# team_flag.net
KiCad netlist of a schematic drawn in EAGLE
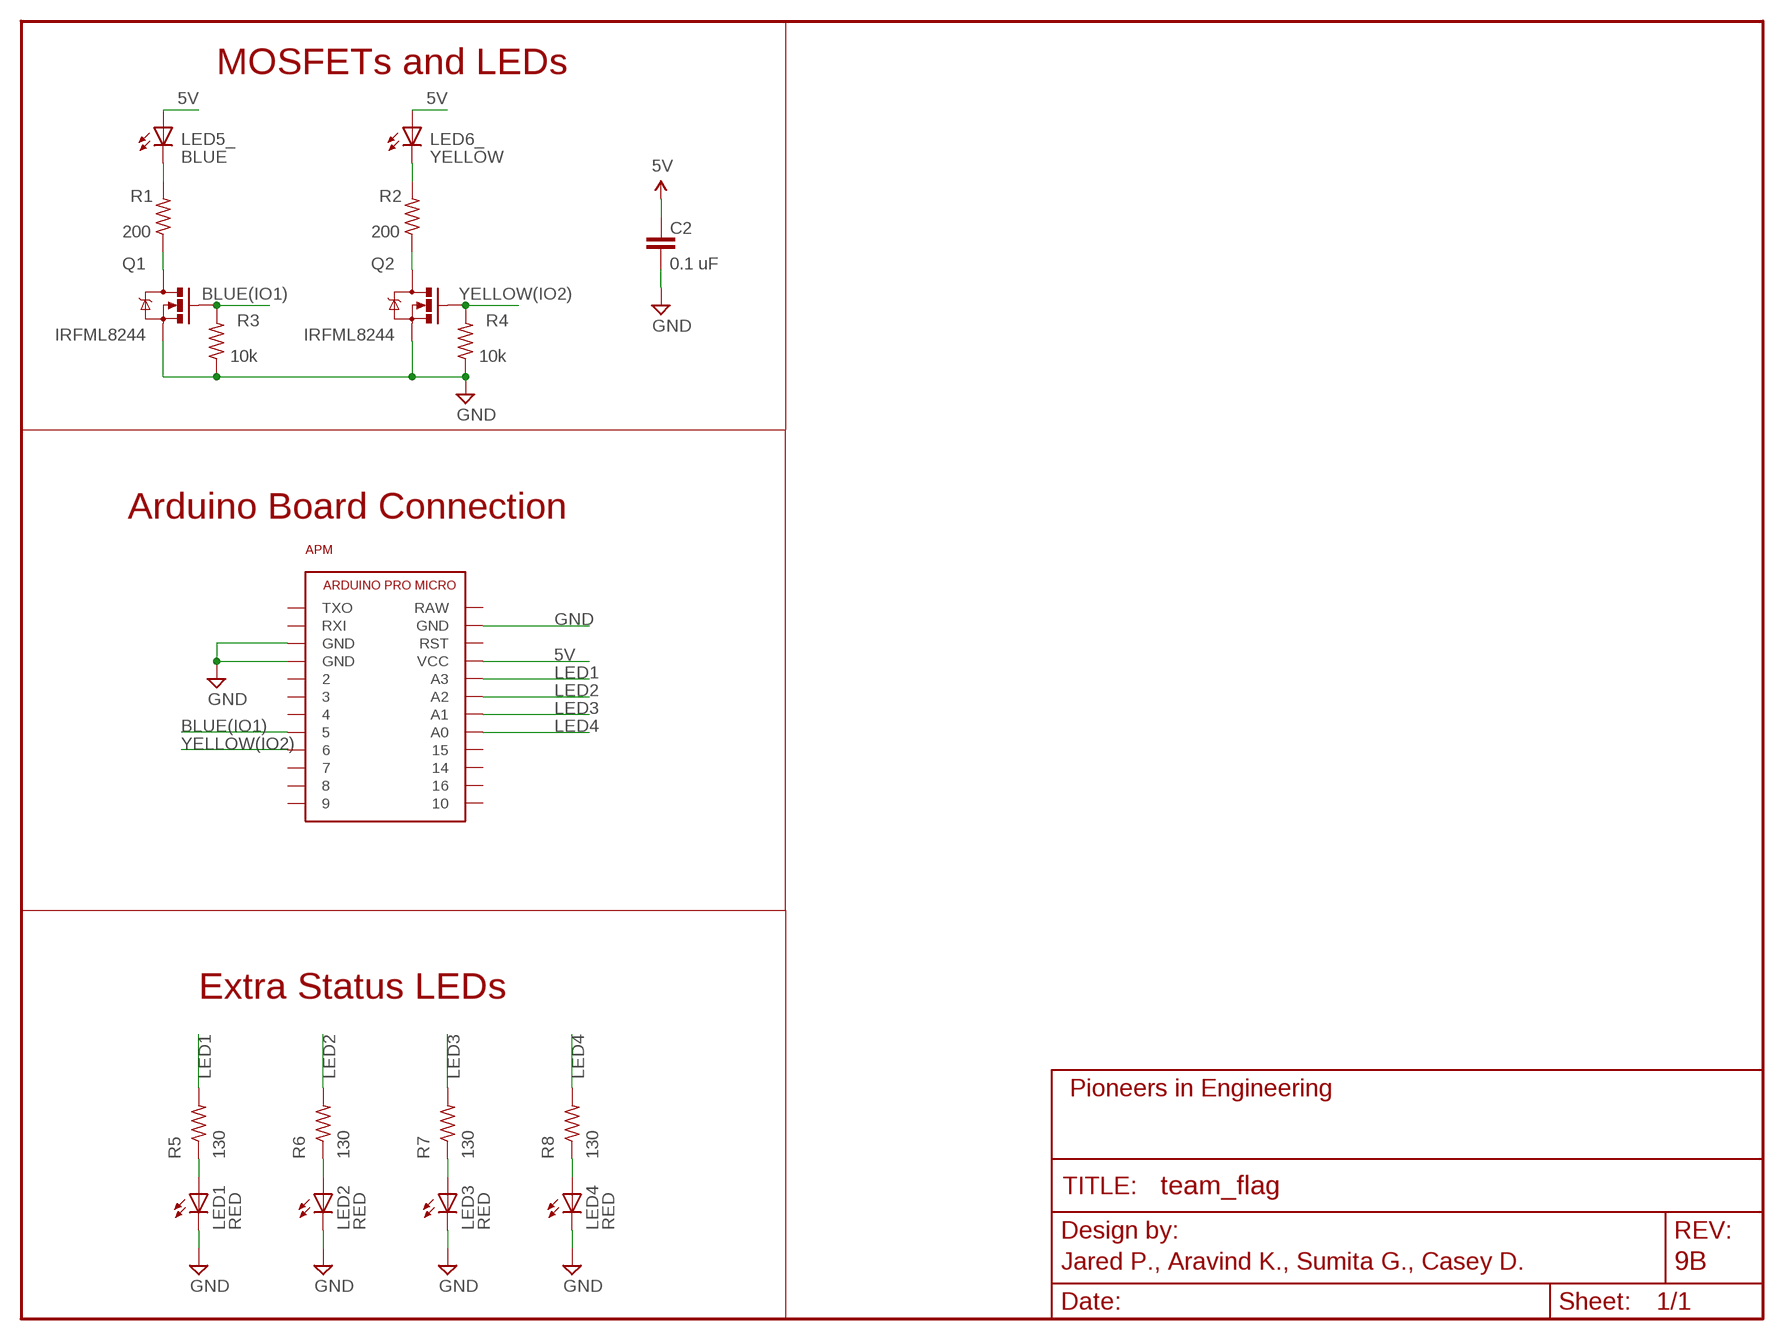
[diagram p0: schematic, sheet 1]

(export (version "E")
  (design (tool "Eeschema 10.0.6"))
  (components
    (comp (ref "APM")
      (value "ARDUINO_PRO_MICRO")
      (footprint "eagle-import:ARDUINO_PRO_MICRO")
      (libsource (lib "eagle-import") (part "ARDUINO_PRO_MICRO"))
    )
    (comp (ref "C2")
      (value "0.1 uF")
      (footprint "eagle-import:0603-CAP")
      (libsource (lib "eagle-import") (part "CAP0603-CAP"))
    )
    (comp (ref "LED1")
      (value "RED")
      (footprint "eagle-import:LED-0805")
      (libsource (lib "eagle-import") (part "LED0805"))
    )
    (comp (ref "LED2")
      (value "RED")
      (footprint "eagle-import:LED-0805")
      (libsource (lib "eagle-import") (part "LED0805"))
    )
    (comp (ref "LED3")
      (value "RED")
      (footprint "eagle-import:LED-0805")
      (libsource (lib "eagle-import") (part "LED0805"))
    )
    (comp (ref "LED4")
      (value "RED")
      (footprint "eagle-import:LED-0805")
      (libsource (lib "eagle-import") (part "LED0805"))
    )
    (comp (ref "LED5_")
      (value "BLUE")
      (footprint "eagle-import:LED5MM-NOFLAT")
      (libsource (lib "eagle-import") (part "LEDLED5MM-NOFLAT"))
    )
    (comp (ref "LED6_")
      (value "YELLOW")
      (footprint "eagle-import:LED5MM-NOFLAT")
      (libsource (lib "eagle-import") (part "LEDLED5MM-NOFLAT"))
    )
    (comp (ref "Q1")
      (value "IRFML8244")
      (footprint "eagle-import:SOT23-3")
      (libsource (lib "eagle-import") (part "MOSFET-NCHANNELSMD"))
    )
    (comp (ref "Q2")
      (value "IRFML8244")
      (footprint "eagle-import:SOT23-3")
      (libsource (lib "eagle-import") (part "MOSFET-NCHANNELSMD"))
    )
    (comp (ref "R1")
      (value "200")
      (footprint "eagle-import:R0603")
      (libsource (lib "eagle-import") (part "R-US_R0603"))
    )
    (comp (ref "R2")
      (value "200")
      (footprint "eagle-import:R0603")
      (libsource (lib "eagle-import") (part "R-US_R0603"))
    )
    (comp (ref "R3")
      (value "10k")
      (footprint "eagle-import:R0603")
      (libsource (lib "eagle-import") (part "R-US_R0603"))
    )
    (comp (ref "R4")
      (value "10k")
      (footprint "eagle-import:R0603")
      (libsource (lib "eagle-import") (part "R-US_R0603"))
    )
    (comp (ref "R5")
      (value "130")
      (footprint "eagle-import:R0603")
      (libsource (lib "eagle-import") (part "R-US_R0603"))
    )
    (comp (ref "R6")
      (value "130")
      (footprint "eagle-import:R0603")
      (libsource (lib "eagle-import") (part "R-US_R0603"))
    )
    (comp (ref "R7")
      (value "130")
      (footprint "eagle-import:R0603")
      (libsource (lib "eagle-import") (part "R-US_R0603"))
    )
    (comp (ref "R8")
      (value "130")
      (footprint "eagle-import:R0603")
      (libsource (lib "eagle-import") (part "R-US_R0603"))
    )
  )
  (nets
    (net (code "1") (name "/BLUE(IO1)") (class "Default")
      (node (ref "APM") (pin "5") (pinfunction "5_5") (pintype "bidirectional"))
      (node (ref "Q1") (pin "1") (pinfunction "G_1") (pintype "passive"))
      (node (ref "R3") (pin "2") (pinfunction "2_2") (pintype "passive"))
    )
    (net (code "2") (name "/LED1") (class "Default")
      (node (ref "APM") (pin "A3") (pinfunction "A3_A3") (pintype "bidirectional"))
      (node (ref "R5") (pin "2") (pinfunction "2_2") (pintype "passive"))
    )
    (net (code "3") (name "/LED2") (class "Default")
      (node (ref "APM") (pin "A2") (pinfunction "A2_A2") (pintype "bidirectional"))
      (node (ref "R6") (pin "2") (pinfunction "2_2") (pintype "passive"))
    )
    (net (code "4") (name "/LED3") (class "Default")
      (node (ref "APM") (pin "A1") (pinfunction "A1_A1") (pintype "bidirectional"))
      (node (ref "R7") (pin "2") (pinfunction "2_2") (pintype "passive"))
    )
    (net (code "5") (name "/LED4") (class "Default")
      (node (ref "APM") (pin "A0") (pinfunction "A0_A0") (pintype "bidirectional"))
      (node (ref "R8") (pin "2") (pinfunction "2_2") (pintype "passive"))
    )
    (net (code "6") (name "/YELLOW(IO2)") (class "Default")
      (node (ref "APM") (pin "6") (pinfunction "6_6") (pintype "bidirectional"))
      (node (ref "Q2") (pin "1") (pinfunction "G_1") (pintype "passive"))
      (node (ref "R4") (pin "2") (pinfunction "2_2") (pintype "passive"))
    )
    (net (code "7") (name "5V") (class "Default")
      (node (ref "APM") (pin "VCC") (pinfunction "VCC_VCC") (pintype "bidirectional"))
      (node (ref "C2") (pin "1") (pinfunction "1_1") (pintype "passive"))
      (node (ref "LED5_") (pin "A") (pinfunction "A_A") (pintype "passive"))
      (node (ref "LED6_") (pin "A") (pinfunction "A_A") (pintype "passive"))
    )
    (net (code "8") (name "GND") (class "Default")
      (node (ref "APM") (pin "GND@0") (pinfunction "GND_GND@0") (pintype "bidirectional"))
      (node (ref "APM") (pin "GND@1") (pinfunction "GND_GND@1") (pintype "bidirectional"))
      (node (ref "APM") (pin "GND@2") (pinfunction "GND_GND@2") (pintype "bidirectional"))
      (node (ref "C2") (pin "2") (pinfunction "2_2") (pintype "passive"))
      (node (ref "LED1") (pin "C") (pinfunction "C_C") (pintype "passive"))
      (node (ref "LED2") (pin "C") (pinfunction "C_C") (pintype "passive"))
      (node (ref "LED3") (pin "C") (pinfunction "C_C") (pintype "passive"))
      (node (ref "LED4") (pin "C") (pinfunction "C_C") (pintype "passive"))
      (node (ref "Q1") (pin "2") (pinfunction "S_2") (pintype "passive"))
      (node (ref "Q2") (pin "2") (pinfunction "S_2") (pintype "passive"))
      (node (ref "R3") (pin "1") (pinfunction "1_1") (pintype "passive"))
      (node (ref "R4") (pin "1") (pinfunction "1_1") (pintype "passive"))
    )
    (net (code "9") (name "Net-(LED1-PadA)") (class "Default")
      (node (ref "LED1") (pin "A") (pinfunction "A_A") (pintype "passive"))
      (node (ref "R5") (pin "1") (pinfunction "1_1") (pintype "passive"))
    )
    (net (code "10") (name "Net-(LED2-PadA)") (class "Default")
      (node (ref "LED2") (pin "A") (pinfunction "A_A") (pintype "passive"))
      (node (ref "R6") (pin "1") (pinfunction "1_1") (pintype "passive"))
    )
    (net (code "11") (name "Net-(LED3-PadA)") (class "Default")
      (node (ref "LED3") (pin "A") (pinfunction "A_A") (pintype "passive"))
      (node (ref "R7") (pin "1") (pinfunction "1_1") (pintype "passive"))
    )
    (net (code "12") (name "Net-(LED4-PadA)") (class "Default")
      (node (ref "LED4") (pin "A") (pinfunction "A_A") (pintype "passive"))
      (node (ref "R8") (pin "1") (pinfunction "1_1") (pintype "passive"))
    )
    (net (code "13") (name "Net-(LED5_-C)") (class "Default")
      (node (ref "LED5_") (pin "K") (pinfunction "C_K") (pintype "passive"))
      (node (ref "R1") (pin "2") (pinfunction "2_2") (pintype "passive"))
    )
    (net (code "14") (name "Net-(LED6_-C)") (class "Default")
      (node (ref "LED6_") (pin "K") (pinfunction "C_K") (pintype "passive"))
      (node (ref "R2") (pin "2") (pinfunction "2_2") (pintype "passive"))
    )
    (net (code "15") (name "Net-(Q1-D)") (class "Default")
      (node (ref "Q1") (pin "3") (pinfunction "D_3") (pintype "passive"))
      (node (ref "R1") (pin "1") (pinfunction "1_1") (pintype "passive"))
    )
    (net (code "16") (name "Net-(Q2-D)") (class "Default")
      (node (ref "Q2") (pin "3") (pinfunction "D_3") (pintype "passive"))
      (node (ref "R2") (pin "1") (pinfunction "1_1") (pintype "passive"))
    )
    (net (code "17") (name "unconnected-(APM-Pad2)") (class "Default")
      (node (ref "APM") (pin "2") (pinfunction "2_2") (pintype "bidirectional"))
    )
    (net (code "18") (name "unconnected-(APM-Pad3)") (class "Default")
      (node (ref "APM") (pin "3") (pinfunction "3_3") (pintype "bidirectional"))
    )
    (net (code "19") (name "unconnected-(APM-Pad4)") (class "Default")
      (node (ref "APM") (pin "4") (pinfunction "4_4") (pintype "bidirectional"))
    )
    (net (code "20") (name "unconnected-(APM-Pad7)") (class "Default")
      (node (ref "APM") (pin "7") (pinfunction "7_7") (pintype "bidirectional"))
    )
    (net (code "21") (name "unconnected-(APM-Pad8)") (class "Default")
      (node (ref "APM") (pin "8") (pinfunction "8_8") (pintype "bidirectional"))
    )
    (net (code "22") (name "unconnected-(APM-Pad9)") (class "Default")
      (node (ref "APM") (pin "9") (pinfunction "9_9") (pintype "bidirectional"))
    )
    (net (code "23") (name "unconnected-(APM-Pad10)") (class "Default")
      (node (ref "APM") (pin "10") (pinfunction "10_10") (pintype "bidirectional"))
    )
    (net (code "24") (name "unconnected-(APM-Pad14)") (class "Default")
      (node (ref "APM") (pin "14") (pinfunction "14_14") (pintype "bidirectional"))
    )
    (net (code "25") (name "unconnected-(APM-Pad15)") (class "Default")
      (node (ref "APM") (pin "15") (pinfunction "15_15") (pintype "bidirectional"))
    )
    (net (code "26") (name "unconnected-(APM-Pad16)") (class "Default")
      (node (ref "APM") (pin "16") (pinfunction "16_16") (pintype "bidirectional"))
    )
    (net (code "27") (name "unconnected-(APM-PadRAW)") (class "Default")
      (node (ref "APM") (pin "RAW") (pinfunction "RAW_RAW") (pintype "bidirectional"))
    )
    (net (code "28") (name "unconnected-(APM-PadRST)") (class "Default")
      (node (ref "APM") (pin "RST") (pinfunction "RST_RST") (pintype "bidirectional"))
    )
    (net (code "29") (name "unconnected-(APM-PadRXI)") (class "Default")
      (node (ref "APM") (pin "RXI") (pinfunction "RXI_RXI") (pintype "bidirectional"))
    )
    (net (code "30") (name "unconnected-(APM-PadTXO)") (class "Default")
      (node (ref "APM") (pin "TXO") (pinfunction "TXO_TXO") (pintype "bidirectional"))
    )
  )
)
